# MAX3232.net
KiCad netlist of a schematic drawn in Altium Designer
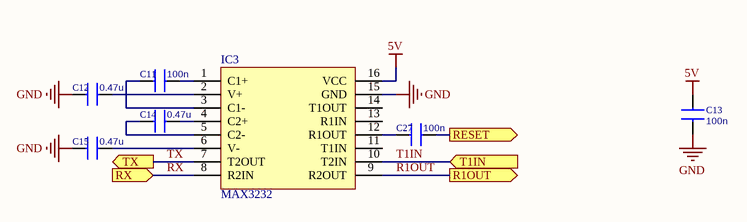
[diagram p0: MAX3232.SchDoc]

(export (version "E")
  (design (tool "Eeschema 10.0.6"))
  (components
    (comp (ref "C11")
      (value "100n")
      (footprint "C_0805")
      (description "Capacitor")
      (libsource (lib "AX_Altium_v2.3") (part "C0805"))
    )
    (comp (ref "C12")
      (value "0.47u")
      (footprint "C_0805")
      (description "Capacitor")
      (libsource (lib "AX_Altium_v2.3") (part "C0805"))
    )
    (comp (ref "C13")
      (value "100n")
      (footprint "C_0805")
      (description "Capacitor")
      (libsource (lib "AX_Altium_v2.3") (part "C0805"))
    )
    (comp (ref "C14")
      (value "0.47u")
      (footprint "C_0805")
      (description "Capacitor")
      (libsource (lib "AX_Altium_v2.3") (part "C0805"))
    )
    (comp (ref "C15")
      (value "0.47u")
      (footprint "C_0805")
      (description "Capacitor")
      (libsource (lib "AX_Altium_v2.3") (part "C0805"))
    )
    (comp (ref "C27")
      (value "100n")
      (footprint "C_0805")
      (description "Capacitor")
      (libsource (lib "AX_Altium_v2.3") (part "C0805"))
    )
    (comp (ref "IC3")
      (value "MAX3232")
      (footprint "SSOP-16")
      (description "RS-232 Line Driver/Receiver With ±15-kV ESD Protection")
      (libsource (lib "SmartOutletIntegratedLibrary") (part "MAX3232"))
    )
  )
  (nets
    (net (code "1") (name "/R1OUT") (class "Default")
      (node (ref "IC3") (pin "9") (pinfunction "R2OUT_9") (pintype "passive"))
    )
    (net (code "2") (name "/RESET") (class "Default") (node (ref "C27") (pin "2") (pintype "passive")))
    (net (code "3") (name "/RX") (class "Default")
      (node (ref "IC3") (pin "8") (pinfunction "R2IN_8") (pintype "passive"))
    )
    (net (code "4") (name "/T1IN") (class "Default")
      (node (ref "IC3") (pin "10") (pinfunction "T2IN_10") (pintype "passive"))
    )
    (net (code "5") (name "/TX") (class "Default")
      (node (ref "IC3") (pin "7") (pinfunction "T2OUT_7") (pintype "passive"))
    )
    (net (code "6") (name "5V") (class "Default")
      (node (ref "C13") (pin "2") (pintype "passive"))
      (node (ref "IC3") (pin "16") (pinfunction "VCC_16") (pintype "passive"))
    )
    (net (code "7") (name "GND") (class "Default")
      (node (ref "C12") (pin "1") (pintype "passive"))
      (node (ref "C13") (pin "1") (pintype "passive"))
      (node (ref "C15") (pin "1") (pintype "passive"))
      (node (ref "IC3") (pin "15") (pinfunction "GND_15") (pintype "passive"))
    )
    (net (code "8") (name "Net-(IC3-C1+)") (class "Default")
      (node (ref "C11") (pin "2") (pintype "passive"))
      (node (ref "IC3") (pin "1") (pinfunction "C1+_1") (pintype "passive"))
    )
    (net (code "9") (name "Net-(IC3-C1-)") (class "Default")
      (node (ref "C11") (pin "1") (pintype "passive"))
      (node (ref "IC3") (pin "3") (pinfunction "C1-_3") (pintype "passive"))
    )
    (net (code "10") (name "Net-(IC3-C2+)") (class "Default")
      (node (ref "C14") (pin "2") (pintype "passive"))
      (node (ref "IC3") (pin "4") (pinfunction "C2+_4") (pintype "passive"))
    )
    (net (code "11") (name "Net-(IC3-C2-)") (class "Default")
      (node (ref "C14") (pin "1") (pintype "passive"))
      (node (ref "IC3") (pin "5") (pinfunction "C2-_5") (pintype "passive"))
    )
    (net (code "12") (name "Net-(IC3-R1OUT)") (class "Default")
      (node (ref "C27") (pin "1") (pintype "passive"))
      (node (ref "IC3") (pin "12") (pinfunction "R1OUT_12") (pintype "passive"))
    )
    (net (code "13") (name "Net-(IC3-V+)") (class "Default")
      (node (ref "C12") (pin "2") (pintype "passive"))
      (node (ref "IC3") (pin "2") (pinfunction "V+_2") (pintype "passive"))
    )
    (net (code "14") (name "Net-(IC3-V-)") (class "Default")
      (node (ref "C15") (pin "2") (pintype "passive"))
      (node (ref "IC3") (pin "6") (pinfunction "V-_6") (pintype "passive"))
    )
    (net (code "15") (name "unconnected-(IC3-R1IN-Pad13)") (class "Default")
      (node (ref "IC3") (pin "13") (pinfunction "R1IN_13") (pintype "passive"))
    )
    (net (code "16") (name "unconnected-(IC3-T1IN-Pad11)") (class "Default")
      (node (ref "IC3") (pin "11") (pinfunction "T1IN_11") (pintype "passive"))
    )
    (net (code "17") (name "unconnected-(IC3-T1OUT-Pad14)") (class "Default")
      (node (ref "IC3") (pin "14") (pinfunction "T1OUT_14") (pintype "passive"))
    )
  )
)
